# Power.net
KiCad netlist of a schematic drawn in Altium Designer
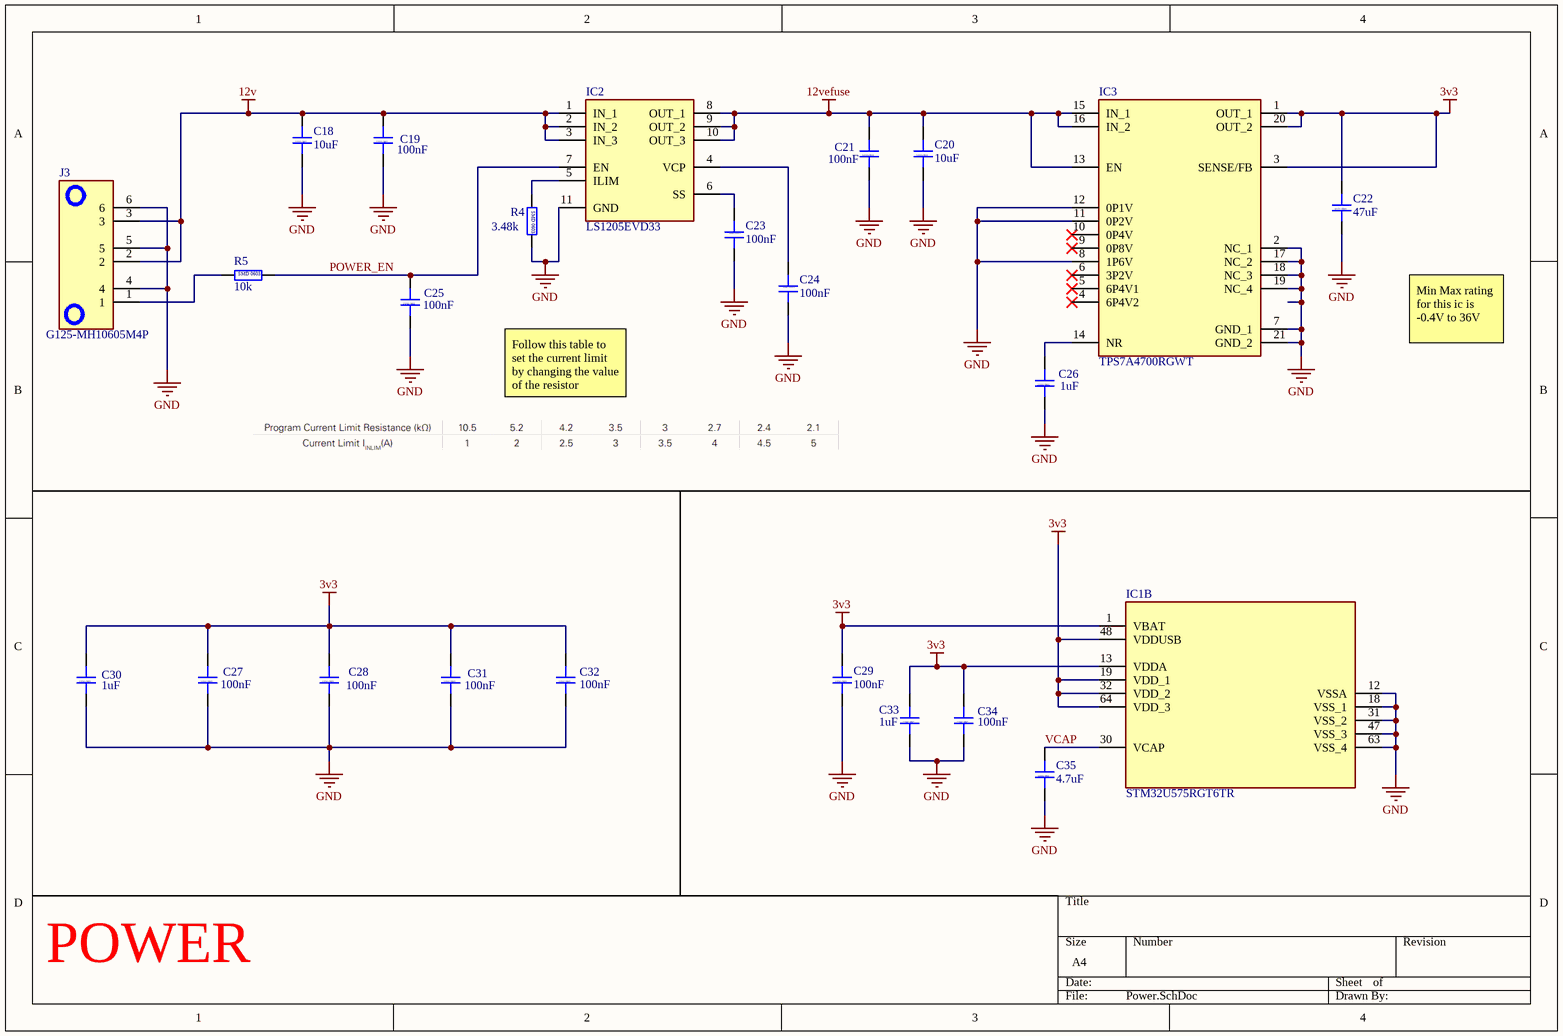
[diagram p0: Power.SchDoc]

(export (version "E")
  (design (tool "Eeschema 10.0.6"))
  (components
    (comp (ref "C18")
      (value "10uF")
      (footprint "CAP_0805")
      (description "Capacitor SMD 0805 RATED")
      (libsource (lib "STeRG-Passives-Standard") (part "Capacitor-SMD-0805"))
    )
    (comp (ref "C19")
      (value "100nF")
      (footprint "CAP_0603")
      (description "Capacitor SMD 0603 RATED")
      (libsource (lib "STeRG-Passives-Standard") (part "Capacitor-SMD-0603"))
    )
    (comp (ref "C20")
      (value "10uF")
      (footprint "CAP_0805")
      (description "Capacitor SMD 0805 RATED")
      (libsource (lib "STeRG-Passives-Standard") (part "Capacitor-SMD-0805"))
    )
    (comp (ref "C21")
      (value "100nF")
      (footprint "CAP_0603")
      (description "Capacitor SMD 0603 RATED")
      (libsource (lib "STeRG-Passives-Standard") (part "Capacitor-SMD-0603"))
    )
    (comp (ref "C22")
      (value "47uF")
      (footprint "CAP_1210")
      (description "Capacitor SMD 1210 RATED")
      (libsource (lib "STeRG-Passives-Standard") (part "Capacitor-SMD-1210"))
    )
    (comp (ref "C23")
      (value "100nF")
      (footprint "CAP_0603")
      (description "Capacitor SMD 0603 RATED")
      (libsource (lib "STeRG-Passives-Standard") (part "Capacitor-SMD-0603"))
    )
    (comp (ref "C24")
      (value "100nF")
      (footprint "CAP_0603")
      (description "Capacitor SMD 0603 RATED")
      (libsource (lib "STeRG-Passives-Standard") (part "Capacitor-SMD-0603"))
    )
    (comp (ref "C25")
      (value "100nF")
      (footprint "CAP_0603")
      (description "Capacitor SMD 0603 RATED")
      (libsource (lib "STeRG-Passives-Standard") (part "Capacitor-SMD-0603"))
    )
    (comp (ref "C26")
      (value "1uF")
      (footprint "CAP_0603")
      (description "Capacitor SMD 0603 RATED")
      (libsource (lib "STeRG-Passives-Standard") (part "Capacitor-SMD-0603"))
    )
    (comp (ref "C27")
      (value "100nF")
      (footprint "CAP_0603")
      (description "Capacitor SMD 0603 RATED")
      (libsource (lib "STeRG-Passives-Standard") (part "Capacitor-SMD-0603"))
    )
    (comp (ref "C28")
      (value "100nF")
      (footprint "CAP_0603")
      (description "Capacitor SMD 0603 RATED")
      (libsource (lib "STeRG-Passives-Standard") (part "Capacitor-SMD-0603"))
    )
    (comp (ref "C29")
      (value "100nF")
      (footprint "CAP_0603")
      (description "Capacitor SMD 0603 RATED")
      (libsource (lib "STeRG-Passives-Standard") (part "Capacitor-SMD-0603"))
    )
    (comp (ref "C30")
      (value "1uF")
      (footprint "CAP_0603")
      (description "Capacitor SMD 0603 RATED")
      (libsource (lib "STeRG-Passives-Standard") (part "Capacitor-SMD-0603"))
    )
    (comp (ref "C31")
      (value "100nF")
      (footprint "CAP_0603")
      (description "Capacitor SMD 0603 RATED")
      (libsource (lib "STeRG-Passives-Standard") (part "Capacitor-SMD-0603"))
    )
    (comp (ref "C32")
      (value "100nF")
      (footprint "CAP_0603")
      (description "Capacitor SMD 0603 RATED")
      (libsource (lib "STeRG-Passives-Standard") (part "Capacitor-SMD-0603"))
    )
    (comp (ref "C33")
      (value "1uF")
      (footprint "CAP_0603")
      (description "Capacitor SMD 0603 RATED")
      (libsource (lib "STeRG-Passives-Standard") (part "Capacitor-SMD-0603"))
    )
    (comp (ref "C34")
      (value "100nF")
      (footprint "CAP_0603")
      (description "Capacitor SMD 0603 RATED")
      (libsource (lib "STeRG-Passives-Standard") (part "Capacitor-SMD-0603"))
    )
    (comp (ref "C35")
      (value "4.7uF")
      (footprint "CAP_0603")
      (description "Capacitor SMD 0603 RATED")
      (libsource (lib "STeRG-Passives-Standard") (part "Capacitor-SMD-0603"))
    )
    (comp (ref "IC1")
      (value "STM32U575RGT6TR")
      (footprint "QFP50P1200X1200X160-64N")
      (description "Integrated Circuit")
      (fields (field (name "MOUSER PART NUMBER") "511-STM32U575RGT6TR"))
      (libsource (lib "STeRG-ICs-Standard") (part "STM32U575RGT6TR"))
    )
    (comp (ref "IC2")
      (value "LS1205EVD33")
      (footprint "SamacSys:LS1205EVD33")
      (description "Integrated Circuit")
      (fields (field (name "MOUSER PART NUMBER") "576-LS1205EVD33"))
      (libsource (lib "SamacSys") (part "LS1205EVD33"))
    )
    (comp (ref "IC3")
      (value "TPS7A4700RGWT")
      (footprint "SamacSys:QFN65P500X500X100-21N-D")
      (description "Integrated Circuit")
      (fields
        (field (name "MANUFACTURER_PART_NUMBER") "TPS7A4700RGWR")
        (field (name "MOUSER PART NUMBER") "595-TPS7A4700RGWR")
      )
      (libsource (lib "SamacSys") (part "TPS7A4700RGWR"))
    )
    (comp (ref "J3")
      (value "G125-MH10605M4P")
      (footprint "G125-MH10605M4P_1")
      (description "Connector")
      (fields (field (name "MOUSER PART NUMBER") "855-G125MH1065M4PM4P"))
      (libsource (lib "STeRG-Passives-Standard") (part "G125-MH10605M4P"))
    )
    (comp (ref "R4")
      (value "3.48k")
      (footprint "RES_0603")
      (description "Resistor SMD 0603 RATED")
      (libsource (lib "STeRG-Passives-Standard") (part "Resistor-SMD-0603"))
    )
    (comp (ref "R5")
      (value "10k")
      (footprint "RES_0603")
      (description "Resistor SMD 0603 RATED")
      (libsource (lib "STeRG-Passives-Standard") (part "Resistor-SMD-0603"))
    )
  )
  (nets
    (net (code "1") (name "/POWER_EN") (class "Default")
      (node (ref "C25") (pin "2") (pinfunction "2_2") (pintype "passive"))
      (node (ref "IC2") (pin "7") (pinfunction "EN_7") (pintype "passive"))
      (node (ref "R5") (pin "2") (pinfunction "2_2") (pintype "passive"))
    )
    (net (code "2") (name "/VCAP") (class "Default")
      (node (ref "C35") (pin "2") (pinfunction "2_2") (pintype "passive"))
      (node (ref "IC1") (pin "30") (pinfunction "VCAP_30") (pintype "passive"))
    )
    (net (code "3") (name "3v3") (class "Default")
      (node (ref "C22") (pin "2") (pinfunction "2_2") (pintype "passive"))
      (node (ref "C27") (pin "2") (pinfunction "2_2") (pintype "passive"))
      (node (ref "C28") (pin "2") (pinfunction "2_2") (pintype "passive"))
      (node (ref "C29") (pin "2") (pinfunction "2_2") (pintype "passive"))
      (node (ref "C30") (pin "2") (pinfunction "2_2") (pintype "passive"))
      (node (ref "C31") (pin "2") (pinfunction "2_2") (pintype "passive"))
      (node (ref "C32") (pin "2") (pinfunction "2_2") (pintype "passive"))
      (node (ref "C33") (pin "2") (pinfunction "2_2") (pintype "passive"))
      (node (ref "C34") (pin "2") (pinfunction "2_2") (pintype "passive"))
      (node (ref "IC1") (pin "1") (pinfunction "VBAT_1") (pintype "passive"))
      (node (ref "IC1") (pin "13") (pinfunction "VDDA_13") (pintype "passive"))
      (node (ref "IC1") (pin "19") (pinfunction "VDD_1_19") (pintype "passive"))
      (node (ref "IC1") (pin "32") (pinfunction "VDD_2_32") (pintype "passive"))
      (node (ref "IC1") (pin "48") (pinfunction "VDDUSB_48") (pintype "passive"))
      (node (ref "IC1") (pin "64") (pinfunction "VDD_3_64") (pintype "passive"))
      (node (ref "IC3") (pin "1") (pinfunction "OUT_1_1") (pintype "passive"))
      (node (ref "IC3") (pin "20") (pinfunction "OUT_2_20") (pintype "passive"))
      (node (ref "IC3") (pin "3") (pinfunction "SENSE/FB_3") (pintype "passive"))
    )
    (net (code "4") (name "12v") (class "Default")
      (node (ref "C18") (pin "2") (pinfunction "2_2") (pintype "passive"))
      (node (ref "C19") (pin "2") (pinfunction "2_2") (pintype "passive"))
      (node (ref "IC2") (pin "1") (pinfunction "IN_1_1") (pintype "passive"))
      (node (ref "IC2") (pin "2") (pinfunction "IN_2_2") (pintype "passive"))
      (node (ref "IC2") (pin "3") (pinfunction "IN_3_3") (pintype "passive"))
      (node (ref "J3") (pin "2") (pinfunction "2_2") (pintype "passive"))
      (node (ref "J3") (pin "3") (pinfunction "3_3") (pintype "passive"))
    )
    (net (code "5") (name "12vefuse") (class "Default")
      (node (ref "C20") (pin "2") (pinfunction "2_2") (pintype "passive"))
      (node (ref "C21") (pin "2") (pinfunction "2_2") (pintype "passive"))
      (node (ref "IC2") (pin "10") (pinfunction "OUT_3_10") (pintype "passive"))
      (node (ref "IC2") (pin "8") (pinfunction "OUT_1_8") (pintype "passive"))
      (node (ref "IC2") (pin "9") (pinfunction "OUT_2_9") (pintype "passive"))
      (node (ref "IC3") (pin "13") (pinfunction "EN_13") (pintype "passive"))
      (node (ref "IC3") (pin "15") (pinfunction "IN_1_15") (pintype "passive"))
      (node (ref "IC3") (pin "16") (pinfunction "IN_2_16") (pintype "passive"))
    )
    (net (code "6") (name "GND") (class "Default")
      (node (ref "C18") (pin "1") (pinfunction "1_1") (pintype "passive"))
      (node (ref "C19") (pin "1") (pinfunction "1_1") (pintype "passive"))
      (node (ref "C20") (pin "1") (pinfunction "1_1") (pintype "passive"))
      (node (ref "C21") (pin "1") (pinfunction "1_1") (pintype "passive"))
      (node (ref "C22") (pin "1") (pinfunction "1_1") (pintype "passive"))
      (node (ref "C23") (pin "2") (pinfunction "2_2") (pintype "passive"))
      (node (ref "C24") (pin "2") (pinfunction "2_2") (pintype "passive"))
      (node (ref "C25") (pin "1") (pinfunction "1_1") (pintype "passive"))
      (node (ref "C26") (pin "1") (pinfunction "1_1") (pintype "passive"))
      (node (ref "C27") (pin "1") (pinfunction "1_1") (pintype "passive"))
      (node (ref "C28") (pin "1") (pinfunction "1_1") (pintype "passive"))
      (node (ref "C29") (pin "1") (pinfunction "1_1") (pintype "passive"))
      (node (ref "C30") (pin "1") (pinfunction "1_1") (pintype "passive"))
      (node (ref "C31") (pin "1") (pinfunction "1_1") (pintype "passive"))
      (node (ref "C32") (pin "1") (pinfunction "1_1") (pintype "passive"))
      (node (ref "C33") (pin "1") (pinfunction "1_1") (pintype "passive"))
      (node (ref "C34") (pin "1") (pinfunction "1_1") (pintype "passive"))
      (node (ref "C35") (pin "1") (pinfunction "1_1") (pintype "passive"))
      (node (ref "IC1") (pin "12") (pinfunction "VSSA_12") (pintype "passive"))
      (node (ref "IC1") (pin "18") (pinfunction "VSS_1_18") (pintype "passive"))
      (node (ref "IC1") (pin "31") (pinfunction "VSS_2_31") (pintype "passive"))
      (node (ref "IC1") (pin "47") (pinfunction "VSS_3_47") (pintype "passive"))
      (node (ref "IC1") (pin "63") (pinfunction "VSS_4_63") (pintype "passive"))
      (node (ref "IC2") (pin "11") (pinfunction "GND_11") (pintype "passive"))
      (node (ref "IC3") (pin "11") (pinfunction "0P2V_11") (pintype "passive"))
      (node (ref "IC3") (pin "12") (pinfunction "0P1V_12") (pintype "passive"))
      (node (ref "IC3") (pin "17") (pinfunction "NC_2_17") (pintype "passive"))
      (node (ref "IC3") (pin "18") (pinfunction "NC_3_18") (pintype "passive"))
      (node (ref "IC3") (pin "19") (pinfunction "NC_4_19") (pintype "passive"))
      (node (ref "IC3") (pin "2") (pinfunction "NC_1_2") (pintype "passive"))
      (node (ref "IC3") (pin "21") (pinfunction "GND_2_21") (pintype "passive"))
      (node (ref "IC3") (pin "7") (pinfunction "GND_1_7") (pintype "passive"))
      (node (ref "IC3") (pin "8") (pinfunction "1P6V_8") (pintype "passive"))
      (node (ref "J3") (pin "4") (pinfunction "4_4") (pintype "passive"))
      (node (ref "J3") (pin "5") (pinfunction "5_5") (pintype "passive"))
      (node (ref "J3") (pin "6") (pinfunction "6_6") (pintype "passive"))
      (node (ref "R4") (pin "2") (pinfunction "2_2") (pintype "passive"))
    )
    (net (code "7") (name "Net-(IC2-ILIM)") (class "Default")
      (node (ref "IC2") (pin "5") (pinfunction "ILIM_5") (pintype "passive"))
      (node (ref "R4") (pin "1") (pinfunction "1_1") (pintype "passive"))
    )
    (net (code "8") (name "Net-(IC2-SS)") (class "Default")
      (node (ref "C23") (pin "1") (pinfunction "1_1") (pintype "passive"))
      (node (ref "IC2") (pin "6") (pinfunction "SS_6") (pintype "passive"))
    )
    (net (code "9") (name "Net-(IC2-VCP)") (class "Default")
      (node (ref "C24") (pin "1") (pinfunction "1_1") (pintype "passive"))
      (node (ref "IC2") (pin "4") (pinfunction "VCP_4") (pintype "passive"))
    )
    (net (code "10") (name "Net-(IC3-NR)") (class "Default")
      (node (ref "C26") (pin "2") (pinfunction "2_2") (pintype "passive"))
      (node (ref "IC3") (pin "14") (pinfunction "NR_14") (pintype "passive"))
    )
    (net (code "11") (name "Net-(J3-Pad1)") (class "Default")
      (node (ref "J3") (pin "1") (pinfunction "1_1") (pintype "passive"))
      (node (ref "R5") (pin "1") (pinfunction "1_1") (pintype "passive"))
    )
    (net (code "12") (name "unconnected-(IC3-0P4V-Pad10)") (class "Default")
      (node (ref "IC3") (pin "10") (pinfunction "0P4V_10") (pintype "passive+no_connect"))
    )
    (net (code "13") (name "unconnected-(IC3-0P8V-Pad9)") (class "Default")
      (node (ref "IC3") (pin "9") (pinfunction "0P8V_9") (pintype "passive+no_connect"))
    )
    (net (code "14") (name "unconnected-(IC3-3P2V-Pad6)") (class "Default")
      (node (ref "IC3") (pin "6") (pinfunction "3P2V_6") (pintype "passive+no_connect"))
    )
    (net (code "15") (name "unconnected-(IC3-6P4V1-Pad5)") (class "Default")
      (node (ref "IC3") (pin "5") (pinfunction "6P4V1_5") (pintype "passive+no_connect"))
    )
    (net (code "16") (name "unconnected-(IC3-6P4V2-Pad4)") (class "Default")
      (node (ref "IC3") (pin "4") (pinfunction "6P4V2_4") (pintype "passive+no_connect"))
    )
  )
)
